# light.net
KiCad netlist of a schematic drawn in EAGLE
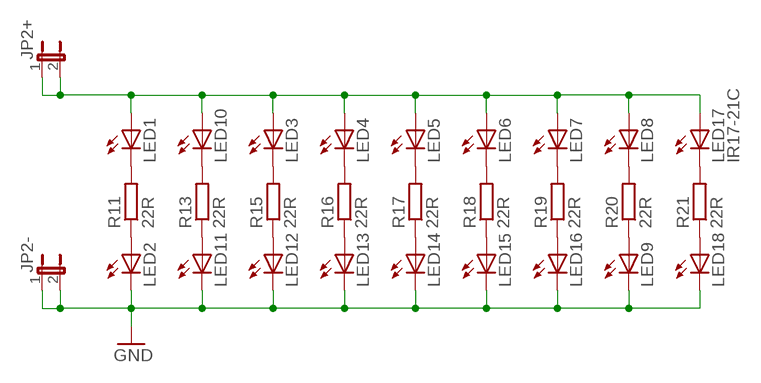
[diagram p0: schematic, sheet 1]

(export (version "E")
  (design (tool "Eeschema 10.0.6"))
  (components
    (comp (ref "JP2+")
      (value "JP1E")
      (footprint "eagle-import:JP1")
      (libsource (lib "eagle-import") (part "JP1E"))
    )
    (comp (ref "JP2-")
      (value "JP1E")
      (footprint "eagle-import:JP1")
      (libsource (lib "eagle-import") (part "JP1E"))
    )
    (comp (ref "LED1")
      (value "LEDCHIPLED_0805")
      (footprint "eagle-import:CHIPLED_0805")
      (libsource (lib "eagle-import") (part "LEDCHIPLED_0805"))
    )
    (comp (ref "LED2")
      (value "LEDCHIPLED_0805")
      (footprint "eagle-import:CHIPLED_0805")
      (libsource (lib "eagle-import") (part "LEDCHIPLED_0805"))
    )
    (comp (ref "LED3")
      (value "LEDCHIPLED_0805")
      (footprint "eagle-import:CHIPLED_0805")
      (libsource (lib "eagle-import") (part "LEDCHIPLED_0805"))
    )
    (comp (ref "LED4")
      (value "LEDCHIPLED_0805")
      (footprint "eagle-import:CHIPLED_0805")
      (libsource (lib "eagle-import") (part "LEDCHIPLED_0805"))
    )
    (comp (ref "LED5")
      (value "LEDCHIPLED_0805")
      (footprint "eagle-import:CHIPLED_0805")
      (libsource (lib "eagle-import") (part "LEDCHIPLED_0805"))
    )
    (comp (ref "LED6")
      (value "LEDCHIPLED_0805")
      (footprint "eagle-import:CHIPLED_0805")
      (libsource (lib "eagle-import") (part "LEDCHIPLED_0805"))
    )
    (comp (ref "LED7")
      (value "LEDCHIPLED_0805")
      (footprint "eagle-import:CHIPLED_0805")
      (libsource (lib "eagle-import") (part "LEDCHIPLED_0805"))
    )
    (comp (ref "LED8")
      (value "LEDCHIPLED_0805")
      (footprint "eagle-import:CHIPLED_0805")
      (libsource (lib "eagle-import") (part "LEDCHIPLED_0805"))
    )
    (comp (ref "LED9")
      (value "LEDCHIPLED_0805")
      (footprint "eagle-import:CHIPLED_0805")
      (libsource (lib "eagle-import") (part "LEDCHIPLED_0805"))
    )
    (comp (ref "LED10")
      (value "LEDCHIPLED_0805")
      (footprint "eagle-import:CHIPLED_0805")
      (libsource (lib "eagle-import") (part "LEDCHIPLED_0805"))
    )
    (comp (ref "LED11")
      (value "LEDCHIPLED_0805")
      (footprint "eagle-import:CHIPLED_0805")
      (libsource (lib "eagle-import") (part "LEDCHIPLED_0805"))
    )
    (comp (ref "LED12")
      (value "LEDCHIPLED_0805")
      (footprint "eagle-import:CHIPLED_0805")
      (libsource (lib "eagle-import") (part "LEDCHIPLED_0805"))
    )
    (comp (ref "LED13")
      (value "LEDCHIPLED_0805")
      (footprint "eagle-import:CHIPLED_0805")
      (libsource (lib "eagle-import") (part "LEDCHIPLED_0805"))
    )
    (comp (ref "LED14")
      (value "LEDCHIPLED_0805")
      (footprint "eagle-import:CHIPLED_0805")
      (libsource (lib "eagle-import") (part "LEDCHIPLED_0805"))
    )
    (comp (ref "LED15")
      (value "LEDCHIPLED_0805")
      (footprint "eagle-import:CHIPLED_0805")
      (libsource (lib "eagle-import") (part "LEDCHIPLED_0805"))
    )
    (comp (ref "LED16")
      (value "LEDCHIPLED_0805")
      (footprint "eagle-import:CHIPLED_0805")
      (libsource (lib "eagle-import") (part "LEDCHIPLED_0805"))
    )
    (comp (ref "LED17")
      (value "IR17-21C")
      (footprint "eagle-import:CHIPLED_0805")
      (libsource (lib "eagle-import") (part "LEDCHIPLED_0805"))
    )
    (comp (ref "LED18")
      (value "LEDCHIPLED_0805")
      (footprint "eagle-import:CHIPLED_0805")
      (libsource (lib "eagle-import") (part "LEDCHIPLED_0805"))
    )
    (comp (ref "R11")
      (value "22R")
      (footprint "eagle-import:M0805")
      (libsource (lib "eagle-import") (part "R-EU_M0805"))
    )
    (comp (ref "R13")
      (value "22R")
      (footprint "eagle-import:M0805")
      (libsource (lib "eagle-import") (part "R-EU_M0805"))
    )
    (comp (ref "R15")
      (value "22R")
      (footprint "eagle-import:M0805")
      (libsource (lib "eagle-import") (part "R-EU_M0805"))
    )
    (comp (ref "R16")
      (value "22R")
      (footprint "eagle-import:M0805")
      (libsource (lib "eagle-import") (part "R-EU_M0805"))
    )
    (comp (ref "R17")
      (value "22R")
      (footprint "eagle-import:M0805")
      (libsource (lib "eagle-import") (part "R-EU_M0805"))
    )
    (comp (ref "R18")
      (value "22R")
      (footprint "eagle-import:M0805")
      (libsource (lib "eagle-import") (part "R-EU_M0805"))
    )
    (comp (ref "R19")
      (value "22R")
      (footprint "eagle-import:M0805")
      (libsource (lib "eagle-import") (part "R-EU_M0805"))
    )
    (comp (ref "R20")
      (value "22R")
      (footprint "eagle-import:M0805")
      (libsource (lib "eagle-import") (part "R-EU_M0805"))
    )
    (comp (ref "R21")
      (value "22R")
      (footprint "eagle-import:M0805")
      (libsource (lib "eagle-import") (part "R-EU_M0805"))
    )
  )
  (nets
    (net (code "1") (name "GND") (class "Default")
      (node (ref "JP2-") (pin "1") (pinfunction "1_1") (pintype "passive"))
      (node (ref "JP2-") (pin "2") (pinfunction "2_2") (pintype "passive"))
      (node (ref "LED11") (pin "C") (pinfunction "C_C") (pintype "passive"))
      (node (ref "LED12") (pin "C") (pinfunction "C_C") (pintype "passive"))
      (node (ref "LED13") (pin "C") (pinfunction "C_C") (pintype "passive"))
      (node (ref "LED14") (pin "C") (pinfunction "C_C") (pintype "passive"))
      (node (ref "LED15") (pin "C") (pinfunction "C_C") (pintype "passive"))
      (node (ref "LED16") (pin "C") (pinfunction "C_C") (pintype "passive"))
      (node (ref "LED18") (pin "C") (pinfunction "C_C") (pintype "passive"))
      (node (ref "LED2") (pin "C") (pinfunction "C_C") (pintype "passive"))
      (node (ref "LED9") (pin "C") (pinfunction "C_C") (pintype "passive"))
    )
    (net (code "2") (name "Net-(JP2+-Pad1)") (class "Default")
      (node (ref "JP2+") (pin "1") (pinfunction "1_1") (pintype "passive"))
      (node (ref "JP2+") (pin "2") (pinfunction "2_2") (pintype "passive"))
      (node (ref "LED1") (pin "A") (pinfunction "A_A") (pintype "passive"))
      (node (ref "LED10") (pin "A") (pinfunction "A_A") (pintype "passive"))
      (node (ref "LED17") (pin "A") (pinfunction "A_A") (pintype "passive"))
      (node (ref "LED3") (pin "A") (pinfunction "A_A") (pintype "passive"))
      (node (ref "LED4") (pin "A") (pinfunction "A_A") (pintype "passive"))
      (node (ref "LED5") (pin "A") (pinfunction "A_A") (pintype "passive"))
      (node (ref "LED6") (pin "A") (pinfunction "A_A") (pintype "passive"))
      (node (ref "LED7") (pin "A") (pinfunction "A_A") (pintype "passive"))
      (node (ref "LED8") (pin "A") (pinfunction "A_A") (pintype "passive"))
    )
    (net (code "3") (name "Net-(LED1-PadC)") (class "Default")
      (node (ref "LED1") (pin "C") (pinfunction "C_C") (pintype "passive"))
      (node (ref "R11") (pin "2") (pinfunction "2_2") (pintype "passive"))
    )
    (net (code "4") (name "Net-(LED2-PadA)") (class "Default")
      (node (ref "LED2") (pin "A") (pinfunction "A_A") (pintype "passive"))
      (node (ref "R11") (pin "1") (pinfunction "1_1") (pintype "passive"))
    )
    (net (code "5") (name "Net-(LED3-PadC)") (class "Default")
      (node (ref "LED3") (pin "C") (pinfunction "C_C") (pintype "passive"))
      (node (ref "R15") (pin "2") (pinfunction "2_2") (pintype "passive"))
    )
    (net (code "6") (name "Net-(LED4-PadC)") (class "Default")
      (node (ref "LED4") (pin "C") (pinfunction "C_C") (pintype "passive"))
      (node (ref "R16") (pin "2") (pinfunction "2_2") (pintype "passive"))
    )
    (net (code "7") (name "Net-(LED5-PadC)") (class "Default")
      (node (ref "LED5") (pin "C") (pinfunction "C_C") (pintype "passive"))
      (node (ref "R17") (pin "2") (pinfunction "2_2") (pintype "passive"))
    )
    (net (code "8") (name "Net-(LED6-PadC)") (class "Default")
      (node (ref "LED6") (pin "C") (pinfunction "C_C") (pintype "passive"))
      (node (ref "R18") (pin "2") (pinfunction "2_2") (pintype "passive"))
    )
    (net (code "9") (name "Net-(LED7-PadC)") (class "Default")
      (node (ref "LED7") (pin "C") (pinfunction "C_C") (pintype "passive"))
      (node (ref "R19") (pin "2") (pinfunction "2_2") (pintype "passive"))
    )
    (net (code "10") (name "Net-(LED8-PadC)") (class "Default")
      (node (ref "LED8") (pin "C") (pinfunction "C_C") (pintype "passive"))
      (node (ref "R20") (pin "2") (pinfunction "2_2") (pintype "passive"))
    )
    (net (code "11") (name "Net-(LED9-PadA)") (class "Default")
      (node (ref "LED9") (pin "A") (pinfunction "A_A") (pintype "passive"))
      (node (ref "R20") (pin "1") (pinfunction "1_1") (pintype "passive"))
    )
    (net (code "12") (name "Net-(LED10-PadC)") (class "Default")
      (node (ref "LED10") (pin "C") (pinfunction "C_C") (pintype "passive"))
      (node (ref "R13") (pin "2") (pinfunction "2_2") (pintype "passive"))
    )
    (net (code "13") (name "Net-(LED11-PadA)") (class "Default")
      (node (ref "LED11") (pin "A") (pinfunction "A_A") (pintype "passive"))
      (node (ref "R13") (pin "1") (pinfunction "1_1") (pintype "passive"))
    )
    (net (code "14") (name "Net-(LED12-PadA)") (class "Default")
      (node (ref "LED12") (pin "A") (pinfunction "A_A") (pintype "passive"))
      (node (ref "R15") (pin "1") (pinfunction "1_1") (pintype "passive"))
    )
    (net (code "15") (name "Net-(LED13-PadA)") (class "Default")
      (node (ref "LED13") (pin "A") (pinfunction "A_A") (pintype "passive"))
      (node (ref "R16") (pin "1") (pinfunction "1_1") (pintype "passive"))
    )
    (net (code "16") (name "Net-(LED14-PadA)") (class "Default")
      (node (ref "LED14") (pin "A") (pinfunction "A_A") (pintype "passive"))
      (node (ref "R17") (pin "1") (pinfunction "1_1") (pintype "passive"))
    )
    (net (code "17") (name "Net-(LED15-PadA)") (class "Default")
      (node (ref "LED15") (pin "A") (pinfunction "A_A") (pintype "passive"))
      (node (ref "R18") (pin "1") (pinfunction "1_1") (pintype "passive"))
    )
    (net (code "18") (name "Net-(LED16-PadA)") (class "Default")
      (node (ref "LED16") (pin "A") (pinfunction "A_A") (pintype "passive"))
      (node (ref "R19") (pin "1") (pinfunction "1_1") (pintype "passive"))
    )
    (net (code "19") (name "Net-(LED17-PadC)") (class "Default")
      (node (ref "LED17") (pin "C") (pinfunction "C_C") (pintype "passive"))
      (node (ref "R21") (pin "2") (pinfunction "2_2") (pintype "passive"))
    )
    (net (code "20") (name "Net-(LED18-PadA)") (class "Default")
      (node (ref "LED18") (pin "A") (pinfunction "A_A") (pintype "passive"))
      (node (ref "R21") (pin "1") (pinfunction "1_1") (pintype "passive"))
    )
  )
)
